# USB_Board.net
KiCad netlist of a schematic drawn in EAGLE
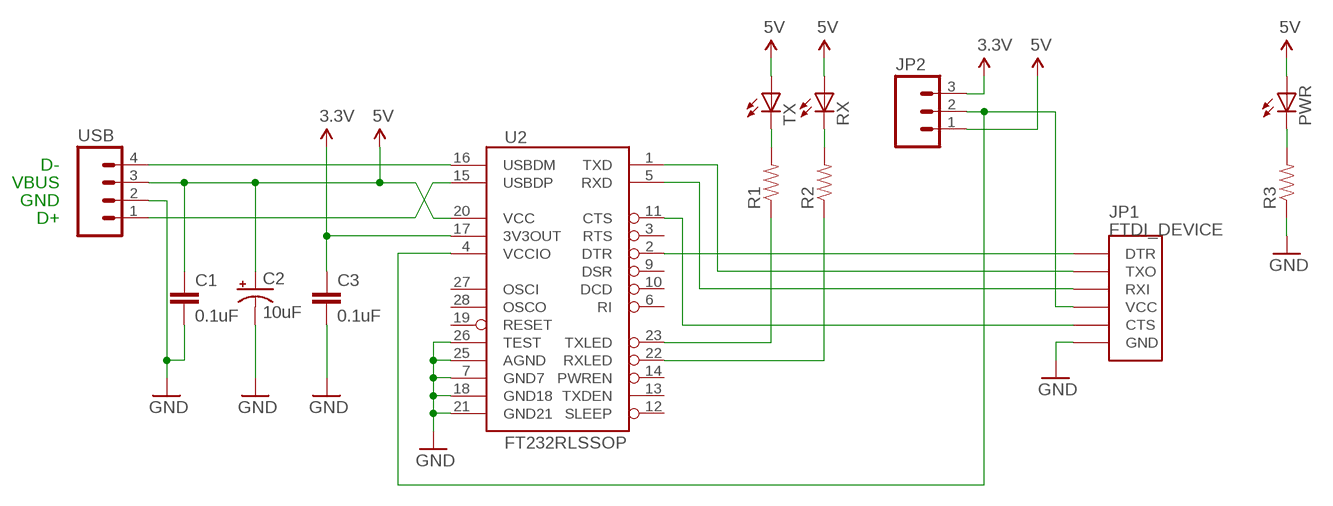
[diagram p0: schematic, sheet 1]

(export (version "E")
  (design (tool "Eeschema 10.0.6"))
  (components
    (comp (ref "C1")
      (value "0.1uF")
      (footprint "eagle-import:CAP-PTH-SMALLEZ")
      (libsource (lib "eagle-import") (part "CAPEZ"))
    )
    (comp (ref "C2")
      (value "10uF")
      (footprint "eagle-import:CPOL-RADIAL-10UF-25V")
      (libsource (lib "eagle-import") (part "CAP_POLPTH2"))
    )
    (comp (ref "C3")
      (value "0.1uF")
      (footprint "eagle-import:CAP-PTH-SMALLEZ")
      (libsource (lib "eagle-import") (part "CAPEZ"))
    )
    (comp (ref "JP1")
      (value "FTDI_DEVICE")
      (footprint "eagle-import:FTDI_DEVICE_SIDE")
      (libsource (lib "eagle-import") (part "FTDI_DEVICE"))
    )
    (comp (ref "JP2")
      (value "M03LOCK")
      (footprint "eagle-import:1X03_LOCK")
      (libsource (lib "eagle-import") (part "M03LOCK"))
    )
    (comp (ref "PWR")
      (value "LED5MM")
      (footprint "eagle-import:LED5MM")
      (libsource (lib "eagle-import") (part "LED5MM"))
    )
    (comp (ref "R1")
      (value "10KOHM1/6W5%(PTH)KIT")
      (footprint "eagle-import:AXIAL-0.3-KIT")
      (libsource (lib "eagle-import") (part "10KOHM1/6W5%(PTH)KIT"))
    )
    (comp (ref "R2")
      (value "10KOHM1/6W5%(PTH)KIT")
      (footprint "eagle-import:AXIAL-0.3-KIT")
      (libsource (lib "eagle-import") (part "10KOHM1/6W5%(PTH)KIT"))
    )
    (comp (ref "R3")
      (value "10KOHM1/6W5%(PTH)KIT")
      (footprint "eagle-import:AXIAL-0.3-KIT")
      (libsource (lib "eagle-import") (part "10KOHM1/6W5%(PTH)KIT"))
    )
    (comp (ref "RX")
      (value "LED5MM")
      (footprint "eagle-import:LED5MM")
      (libsource (lib "eagle-import") (part "LED5MM"))
    )
    (comp (ref "TX")
      (value "LED5MM")
      (footprint "eagle-import:LED5MM")
      (libsource (lib "eagle-import") (part "LED5MM"))
    )
    (comp (ref "U2")
      (value "FT232RLSSOP")
      (footprint "eagle-import:SSOP28DB")
      (libsource (lib "eagle-import") (part "FT232RLSSOP"))
    )
    (comp (ref "USB")
      (value "M04LOCK")
      (footprint "eagle-import:1X04_LOCK")
      (libsource (lib "eagle-import") (part "M04LOCK"))
    )
  )
  (nets
    (net (code "1") (name "3.3V") (class "Default")
      (node (ref "C3") (pin "1") (pinfunction "1_1") (pintype "passive"))
      (node (ref "JP2") (pin "3") (pinfunction "3_3") (pintype "passive"))
      (node (ref "U2") (pin "17") (pinfunction "3V3OUT_17") (pintype "output"))
    )
    (net (code "2") (name "5V") (class "Default")
      (node (ref "C1") (pin "1") (pinfunction "1_1") (pintype "passive"))
      (node (ref "C2") (pin "1") (pinfunction "+_1") (pintype "passive"))
      (node (ref "JP2") (pin "1") (pinfunction "1_1") (pintype "passive"))
      (node (ref "PWR") (pin "A") (pinfunction "A_A") (pintype "passive"))
      (node (ref "RX") (pin "A") (pinfunction "A_A") (pintype "passive"))
      (node (ref "TX") (pin "A") (pinfunction "A_A") (pintype "passive"))
      (node (ref "U2") (pin "20") (pinfunction "VCC_20") (pintype "power_in"))
      (node (ref "USB") (pin "3") (pinfunction "3_3") (pintype "passive"))
    )
    (net (code "3") (name "GND") (class "Default")
      (node (ref "C1") (pin "2") (pinfunction "2_2") (pintype "passive"))
      (node (ref "C2") (pin "2") (pinfunction "-_2") (pintype "passive"))
      (node (ref "C3") (pin "2") (pinfunction "2_2") (pintype "passive"))
      (node (ref "JP1") (pin "P$6") (pinfunction "GND_P$6") (pintype "bidirectional"))
      (node (ref "R3") (pin "P$1") (pinfunction "1_P$1") (pintype "passive"))
      (node (ref "U2") (pin "18") (pinfunction "GND18_18") (pintype "power_in"))
      (node (ref "U2") (pin "21") (pinfunction "GND21_21") (pintype "power_in"))
      (node (ref "U2") (pin "25") (pinfunction "AGND_25") (pintype "power_in"))
      (node (ref "U2") (pin "26") (pinfunction "TEST_26") (pintype "input"))
      (node (ref "U2") (pin "7") (pinfunction "GND7_7") (pintype "power_in"))
      (node (ref "USB") (pin "2") (pinfunction "2_2") (pintype "passive"))
    )
    (net (code "4") (name "Net-(JP1-CTS)") (class "Default")
      (node (ref "JP1") (pin "P$5") (pinfunction "CTS_P$5") (pintype "bidirectional"))
      (node (ref "U2") (pin "11") (pinfunction "CTS_11") (pintype "input"))
    )
    (net (code "5") (name "Net-(JP1-DTR)") (class "Default")
      (node (ref "JP1") (pin "P$1") (pinfunction "DTR_P$1") (pintype "bidirectional"))
      (node (ref "U2") (pin "2") (pinfunction "DTR_2") (pintype "output"))
    )
    (net (code "6") (name "Net-(JP1-RXI)") (class "Default")
      (node (ref "JP1") (pin "P$3") (pinfunction "RXI_P$3") (pintype "bidirectional"))
      (node (ref "U2") (pin "5") (pinfunction "RXD_5") (pintype "input"))
    )
    (net (code "7") (name "Net-(JP1-TXO)") (class "Default")
      (node (ref "JP1") (pin "P$2") (pinfunction "TXO_P$2") (pintype "bidirectional"))
      (node (ref "U2") (pin "1") (pinfunction "TXD_1") (pintype "output"))
    )
    (net (code "8") (name "Net-(JP1-VCC)") (class "Default")
      (node (ref "JP1") (pin "P$4") (pinfunction "VCC_P$4") (pintype "bidirectional"))
      (node (ref "JP2") (pin "2") (pinfunction "2_2") (pintype "passive"))
      (node (ref "U2") (pin "4") (pinfunction "VCCIO_4") (pintype "power_in"))
    )
    (net (code "9") (name "Net-(PWR-C)") (class "Default")
      (node (ref "PWR") (pin "K") (pinfunction "C_K") (pintype "passive"))
      (node (ref "R3") (pin "P$2") (pinfunction "2_P$2") (pintype "passive"))
    )
    (net (code "10") (name "Net-(R1-1)") (class "Default")
      (node (ref "R1") (pin "P$1") (pinfunction "1_P$1") (pintype "passive"))
      (node (ref "U2") (pin "23") (pinfunction "TXLED_23") (pintype "input"))
    )
    (net (code "11") (name "Net-(R1-2)") (class "Default")
      (node (ref "R1") (pin "P$2") (pinfunction "2_P$2") (pintype "passive"))
      (node (ref "TX") (pin "K") (pinfunction "C_K") (pintype "passive"))
    )
    (net (code "12") (name "Net-(R2-1)") (class "Default")
      (node (ref "R2") (pin "P$1") (pinfunction "1_P$1") (pintype "passive"))
      (node (ref "U2") (pin "22") (pinfunction "RXLED_22") (pintype "input"))
    )
    (net (code "13") (name "Net-(R2-2)") (class "Default")
      (node (ref "R2") (pin "P$2") (pinfunction "2_P$2") (pintype "passive"))
      (node (ref "RX") (pin "K") (pinfunction "C_K") (pintype "passive"))
    )
    (net (code "14") (name "Net-(U2-USBDM)") (class "Default")
      (node (ref "U2") (pin "16") (pinfunction "USBDM_16") (pintype "bidirectional"))
      (node (ref "USB") (pin "4") (pinfunction "4_4") (pintype "passive"))
    )
    (net (code "15") (name "Net-(U2-USBDP)") (class "Default")
      (node (ref "U2") (pin "15") (pinfunction "USBDP_15") (pintype "bidirectional"))
      (node (ref "USB") (pin "1") (pinfunction "1_1") (pintype "passive"))
    )
    (net (code "16") (name "unconnected-(U2-DCD-Pad10)") (class "Default")
      (node (ref "U2") (pin "10") (pinfunction "DCD_10") (pintype "input"))
    )
    (net (code "17") (name "unconnected-(U2-DSR-Pad9)") (class "Default")
      (node (ref "U2") (pin "9") (pinfunction "DSR_9") (pintype "input"))
    )
    (net (code "18") (name "unconnected-(U2-OSCI-Pad27)") (class "Default")
      (node (ref "U2") (pin "27") (pinfunction "OSCI_27") (pintype "input"))
    )
    (net (code "19") (name "unconnected-(U2-OSCO-Pad28)") (class "Default")
      (node (ref "U2") (pin "28") (pinfunction "OSCO_28") (pintype "output"))
    )
    (net (code "20") (name "unconnected-(U2-PWREN-Pad14)") (class "Default")
      (node (ref "U2") (pin "14") (pinfunction "PWREN_14") (pintype "input"))
    )
    (net (code "21") (name "unconnected-(U2-RESET-Pad19)") (class "Default")
      (node (ref "U2") (pin "19") (pinfunction "RESET_19") (pintype "input"))
    )
    (net (code "22") (name "unconnected-(U2-RI-Pad6)") (class "Default")
      (node (ref "U2") (pin "6") (pinfunction "RI_6") (pintype "input"))
    )
    (net (code "23") (name "unconnected-(U2-RTS-Pad3)") (class "Default")
      (node (ref "U2") (pin "3") (pinfunction "RTS_3") (pintype "output"))
    )
    (net (code "24") (name "unconnected-(U2-SLEEP-Pad12)") (class "Default")
      (node (ref "U2") (pin "12") (pinfunction "SLEEP_12") (pintype "input"))
    )
    (net (code "25") (name "unconnected-(U2-TXDEN-Pad13)") (class "Default")
      (node (ref "U2") (pin "13") (pinfunction "TXDEN_13") (pintype "input"))
    )
  )
)
